# CU.net
KiCad netlist of a schematic drawn in EAGLE
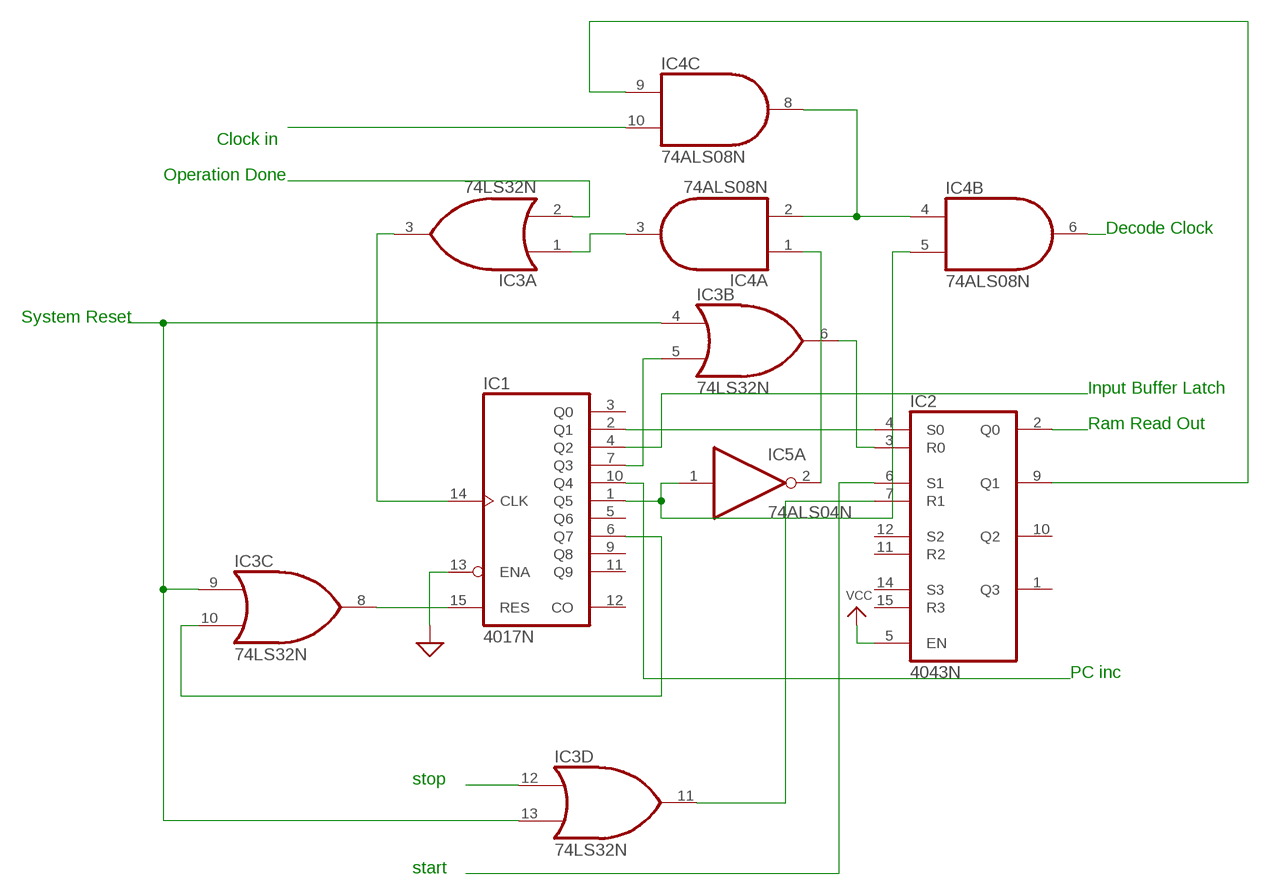
[diagram p0: schematic, sheet 1]

(export (version "E")
  (design (tool "Eeschema 10.0.6"))
  (components
    (comp (ref "IC1")
      (value "4017N")
      (footprint "eagle-import:DIL16")
      (libsource (lib "eagle-import") (part "4017N"))
    )
    (comp (ref "IC2")
      (value "4043N")
      (footprint "eagle-import:DIL16")
      (libsource (lib "eagle-import") (part "4043N"))
    )
    (comp (ref "IC3")
      (value "74LS32N")
      (footprint "eagle-import:DIL14")
      (libsource (lib "eagle-import") (part "7432NLS"))
    )
    (comp (ref "IC4")
      (value "74ALS08N")
      (footprint "eagle-import:DIL14")
      (libsource (lib "eagle-import") (part "7408NALS"))
    )
    (comp (ref "IC5")
      (value "74ALS04N")
      (footprint "eagle-import:DIL14")
      (libsource (lib "eagle-import") (part "7404NALS"))
    )
  )
  (nets
    (net (code "1") (name "Net-(IC1A-CLK)") (class "Default")
      (node (ref "IC1") (pin "14") (pinfunction "CLK_14") (pintype "input"))
      (node (ref "IC3") (pin "3") (pinfunction "O_3") (pintype "output"))
    )
    (net (code "2") (name "Net-(IC1A-Q1)") (class "Default")
      (node (ref "IC1") (pin "2") (pinfunction "Q1_2") (pintype "output"))
      (node (ref "IC2") (pin "4") (pinfunction "S0_4") (pintype "input"))
    )
    (net (code "3") (name "Net-(IC1A-Q3)") (class "Default")
      (node (ref "IC1") (pin "7") (pinfunction "Q3_7") (pintype "output"))
      (node (ref "IC3") (pin "5") (pinfunction "I1_5") (pintype "input"))
    )
    (net (code "4") (name "Net-(IC1A-Q5)") (class "Default")
      (node (ref "IC1") (pin "1") (pinfunction "Q5_1") (pintype "output"))
      (node (ref "IC4") (pin "5") (pinfunction "I1_5") (pintype "input"))
      (node (ref "IC5") (pin "1") (pinfunction "I_1") (pintype "input"))
    )
    (net (code "5") (name "Net-(IC1A-Q7)") (class "Default")
      (node (ref "IC1") (pin "6") (pinfunction "Q7_6") (pintype "output"))
      (node (ref "IC3") (pin "10") (pinfunction "I1_10") (pintype "input"))
    )
    (net (code "6") (name "Net-(IC1A-RES)") (class "Default")
      (node (ref "IC1") (pin "15") (pinfunction "RES_15") (pintype "input"))
      (node (ref "IC3") (pin "8") (pinfunction "O_8") (pintype "output"))
    )
    (net (code "7") (name "Net-(IC2A-Q1)") (class "Default")
      (node (ref "IC2") (pin "9") (pinfunction "Q1_9") (pintype "output"))
      (node (ref "IC4") (pin "9") (pinfunction "I0_9") (pintype "input"))
    )
    (net (code "8") (name "Net-(IC2A-R0)") (class "Default")
      (node (ref "IC2") (pin "3") (pinfunction "R0_3") (pintype "input"))
      (node (ref "IC3") (pin "6") (pinfunction "O_6") (pintype "output"))
    )
    (net (code "9") (name "Net-(IC2A-R1)") (class "Default")
      (node (ref "IC2") (pin "7") (pinfunction "R1_7") (pintype "input"))
      (node (ref "IC3") (pin "11") (pinfunction "O_11") (pintype "output"))
    )
    (net (code "10") (name "Net-(IC3A-I0)") (class "Default")
      (node (ref "IC3") (pin "1") (pinfunction "I0_1") (pintype "input"))
      (node (ref "IC4") (pin "3") (pinfunction "O_3") (pintype "output"))
    )
    (net (code "11") (name "Net-(IC3B-I0)") (class "Default")
      (node (ref "IC3") (pin "13") (pinfunction "I1_13") (pintype "input"))
      (node (ref "IC3") (pin "4") (pinfunction "I0_4") (pintype "input"))
      (node (ref "IC3") (pin "9") (pinfunction "I0_9") (pintype "input"))
    )
    (net (code "12") (name "Net-(IC4A-I0)") (class "Default")
      (node (ref "IC4") (pin "1") (pinfunction "I0_1") (pintype "input"))
      (node (ref "IC5") (pin "2") (pinfunction "O_2") (pintype "output"))
    )
    (net (code "13") (name "Net-(IC4A-I1)") (class "Default")
      (node (ref "IC4") (pin "2") (pinfunction "I1_2") (pintype "input"))
      (node (ref "IC4") (pin "4") (pinfunction "I0_4") (pintype "input"))
      (node (ref "IC4") (pin "8") (pinfunction "O_8") (pintype "output"))
    )
    (net (code "14") (name "SUP") (class "Default")
      (node (ref "IC1") (pin "13") (pinfunction "ENA_13") (pintype "input"))
    )
    (net (code "15") (name "VCC") (class "Default")
      (node (ref "IC2") (pin "5") (pinfunction "EN_5") (pintype "input"))
    )
    (net (code "16") (name "unconnected-(IC1A-CO-Pad12)") (class "Default")
      (node (ref "IC1") (pin "12") (pinfunction "CO_12") (pintype "output"))
    )
    (net (code "17") (name "unconnected-(IC1A-Q0-Pad3)") (class "Default")
      (node (ref "IC1") (pin "3") (pinfunction "Q0_3") (pintype "output"))
    )
    (net (code "18") (name "unconnected-(IC1A-Q2-Pad4)") (class "Default")
      (node (ref "IC1") (pin "4") (pinfunction "Q2_4") (pintype "output"))
    )
    (net (code "19") (name "unconnected-(IC1A-Q4-Pad10)") (class "Default")
      (node (ref "IC1") (pin "10") (pinfunction "Q4_10") (pintype "output"))
    )
    (net (code "20") (name "unconnected-(IC1A-Q6-Pad5)") (class "Default")
      (node (ref "IC1") (pin "5") (pinfunction "Q6_5") (pintype "output"))
    )
    (net (code "21") (name "unconnected-(IC1A-Q8-Pad9)") (class "Default")
      (node (ref "IC1") (pin "9") (pinfunction "Q8_9") (pintype "output"))
    )
    (net (code "22") (name "unconnected-(IC1A-Q9-Pad11)") (class "Default")
      (node (ref "IC1") (pin "11") (pinfunction "Q9_11") (pintype "output"))
    )
    (net (code "23") (name "unconnected-(IC2A-Q0-Pad2)") (class "Default")
      (node (ref "IC2") (pin "2") (pinfunction "Q0_2") (pintype "output"))
    )
    (net (code "24") (name "unconnected-(IC2A-Q2-Pad10)") (class "Default")
      (node (ref "IC2") (pin "10") (pinfunction "Q2_10") (pintype "output"))
    )
    (net (code "25") (name "unconnected-(IC2A-Q3-Pad1)") (class "Default")
      (node (ref "IC2") (pin "1") (pinfunction "Q3_1") (pintype "output"))
    )
    (net (code "26") (name "unconnected-(IC2A-R2-Pad11)") (class "Default")
      (node (ref "IC2") (pin "11") (pinfunction "R2_11") (pintype "input"))
    )
    (net (code "27") (name "unconnected-(IC2A-R3-Pad15)") (class "Default")
      (node (ref "IC2") (pin "15") (pinfunction "R3_15") (pintype "input"))
    )
    (net (code "28") (name "unconnected-(IC2A-S1-Pad6)") (class "Default")
      (node (ref "IC2") (pin "6") (pinfunction "S1_6") (pintype "input"))
    )
    (net (code "29") (name "unconnected-(IC2A-S2-Pad12)") (class "Default")
      (node (ref "IC2") (pin "12") (pinfunction "S2_12") (pintype "input"))
    )
    (net (code "30") (name "unconnected-(IC2A-S3-Pad14)") (class "Default")
      (node (ref "IC2") (pin "14") (pinfunction "S3_14") (pintype "input"))
    )
    (net (code "31") (name "unconnected-(IC3A-I1-Pad2)") (class "Default")
      (node (ref "IC3") (pin "2") (pinfunction "I1_2") (pintype "input"))
    )
    (net (code "32") (name "unconnected-(IC3D-I0-Pad12)") (class "Default")
      (node (ref "IC3") (pin "12") (pinfunction "I0_12") (pintype "input"))
    )
    (net (code "33") (name "unconnected-(IC4B-O-Pad6)") (class "Default")
      (node (ref "IC4") (pin "6") (pinfunction "O_6") (pintype "output"))
    )
    (net (code "34") (name "unconnected-(IC4C-I1-Pad10)") (class "Default")
      (node (ref "IC4") (pin "10") (pinfunction "I1_10") (pintype "input"))
    )
  )
)
